# LCD_ADS131A04.net
KiCad netlist of a schematic drawn in Altium Designer
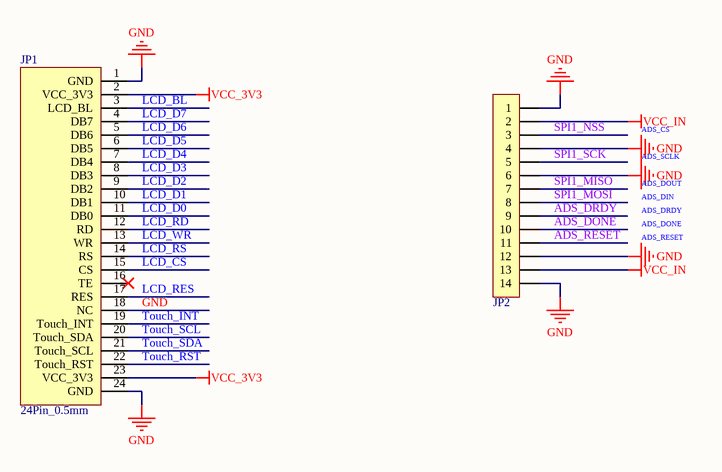
[diagram p0: LCD_ADS131A04.SchDoc]

(export (version "E")
  (design (tool "Eeschema 10.0.6"))
  (components
    (comp (ref "JP1")
      (value "24Pin_0.5mm")
      (footprint "FPC0.5-WT-24P")
      (description "屏幕板外接座")
      (libsource (lib "USER_Lib") (part "屏幕板FPC"))
    )
    (comp (ref "JP2")
      (value "HDR-1X14")
      (footprint "FPC0.5-WT-14P")
      (description "14P接插件")
      (libsource (lib "5.5 - 2.54mm(100mil)连接器(XH2.54)") (part "Header 14"))
    )
  )
  (nets
    (net (code "1") (name "/ADS_DONE") (class "Default")
      (node (ref "JP2") (pin "10") (pinfunction "10_10") (pintype "passive"))
    )
    (net (code "2") (name "/ADS_DRDY") (class "Default")
      (node (ref "JP2") (pin "9") (pinfunction "9_9") (pintype "passive"))
    )
    (net (code "3") (name "/ADS_RESET") (class "Default")
      (node (ref "JP2") (pin "11") (pinfunction "11_11") (pintype "passive"))
    )
    (net (code "4") (name "/LCD_BL") (class "Default")
      (node (ref "JP1") (pin "3") (pinfunction "LCD_BL_3") (pintype "passive"))
    )
    (net (code "5") (name "/LCD_CS") (class "Default")
      (node (ref "JP1") (pin "15") (pinfunction "CS_15") (pintype "passive"))
    )
    (net (code "6") (name "/LCD_D0") (class "Default")
      (node (ref "JP1") (pin "11") (pinfunction "DB0_11") (pintype "passive"))
    )
    (net (code "7") (name "/LCD_D1") (class "Default")
      (node (ref "JP1") (pin "10") (pinfunction "DB1_10") (pintype "passive"))
    )
    (net (code "8") (name "/LCD_D2") (class "Default")
      (node (ref "JP1") (pin "9") (pinfunction "DB2_9") (pintype "passive"))
    )
    (net (code "9") (name "/LCD_D3") (class "Default")
      (node (ref "JP1") (pin "8") (pinfunction "DB3_8") (pintype "passive"))
    )
    (net (code "10") (name "/LCD_D4") (class "Default")
      (node (ref "JP1") (pin "7") (pinfunction "DB4_7") (pintype "passive"))
    )
    (net (code "11") (name "/LCD_D5") (class "Default")
      (node (ref "JP1") (pin "6") (pinfunction "DB5_6") (pintype "passive"))
    )
    (net (code "12") (name "/LCD_D6") (class "Default")
      (node (ref "JP1") (pin "5") (pinfunction "DB6_5") (pintype "passive"))
    )
    (net (code "13") (name "/LCD_D7") (class "Default")
      (node (ref "JP1") (pin "4") (pinfunction "DB7_4") (pintype "passive"))
    )
    (net (code "14") (name "/LCD_RD") (class "Default")
      (node (ref "JP1") (pin "12") (pinfunction "RD_12") (pintype "passive"))
    )
    (net (code "15") (name "/LCD_RES") (class "Default")
      (node (ref "JP1") (pin "17") (pinfunction "RES_17") (pintype "passive"))
    )
    (net (code "16") (name "/LCD_RS") (class "Default")
      (node (ref "JP1") (pin "14") (pinfunction "RS_14") (pintype "passive"))
    )
    (net (code "17") (name "/LCD_WR") (class "Default")
      (node (ref "JP1") (pin "13") (pinfunction "WR_13") (pintype "passive"))
    )
    (net (code "18") (name "/SPI1_MISO") (class "Default")
      (node (ref "JP2") (pin "7") (pinfunction "7_7") (pintype "passive"))
    )
    (net (code "19") (name "/SPI1_MOSI") (class "Default")
      (node (ref "JP2") (pin "8") (pinfunction "8_8") (pintype "passive"))
    )
    (net (code "20") (name "/SPI1_NSS") (class "Default")
      (node (ref "JP2") (pin "3") (pinfunction "3_3") (pintype "passive"))
    )
    (net (code "21") (name "/SPI1_SCK") (class "Default")
      (node (ref "JP2") (pin "5") (pinfunction "5_5") (pintype "passive"))
    )
    (net (code "22") (name "/Touch_INT") (class "Default")
      (node (ref "JP1") (pin "19") (pinfunction "Touch_INT_19") (pintype "passive"))
    )
    (net (code "23") (name "/Touch_RST") (class "Default")
      (node (ref "JP1") (pin "22") (pinfunction "Touch_RST_22") (pintype "passive"))
    )
    (net (code "24") (name "/Touch_SCL") (class "Default")
      (node (ref "JP1") (pin "20") (pinfunction "Touch_SDA_20") (pintype "passive"))
    )
    (net (code "25") (name "/Touch_SDA") (class "Default")
      (node (ref "JP1") (pin "21") (pinfunction "Touch_SCL_21") (pintype "passive"))
    )
    (net (code "26") (name "GND") (class "Default")
      (node (ref "JP1") (pin "1") (pinfunction "GND_1") (pintype "passive"))
      (node (ref "JP1") (pin "18") (pinfunction "NC_18") (pintype "passive"))
      (node (ref "JP1") (pin "24") (pinfunction "GND_24") (pintype "passive"))
      (node (ref "JP2") (pin "1") (pinfunction "1_1") (pintype "passive"))
      (node (ref "JP2") (pin "12") (pinfunction "12_12") (pintype "passive"))
      (node (ref "JP2") (pin "14") (pinfunction "14_14") (pintype "passive"))
      (node (ref "JP2") (pin "4") (pinfunction "4_4") (pintype "passive"))
      (node (ref "JP2") (pin "6") (pinfunction "6_6") (pintype "passive"))
    )
    (net (code "27") (name "VCC_3V3") (class "Default")
      (node (ref "JP1") (pin "2") (pinfunction "VCC_3V3_2") (pintype "passive"))
      (node (ref "JP1") (pin "23") (pinfunction "VCC_3V3_23") (pintype "passive"))
    )
    (net (code "28") (name "VCC_IN") (class "Default")
      (node (ref "JP2") (pin "13") (pinfunction "13_13") (pintype "passive"))
      (node (ref "JP2") (pin "2") (pinfunction "2_2") (pintype "passive"))
    )
    (net (code "29") (name "unconnected-(JP1-TE-Pad16)") (class "Default")
      (node (ref "JP1") (pin "16") (pinfunction "TE_16") (pintype "passive+no_connect"))
    )
  )
)
